# Spanungsversorgung.net
KiCad netlist of a schematic drawn in Altium Designer
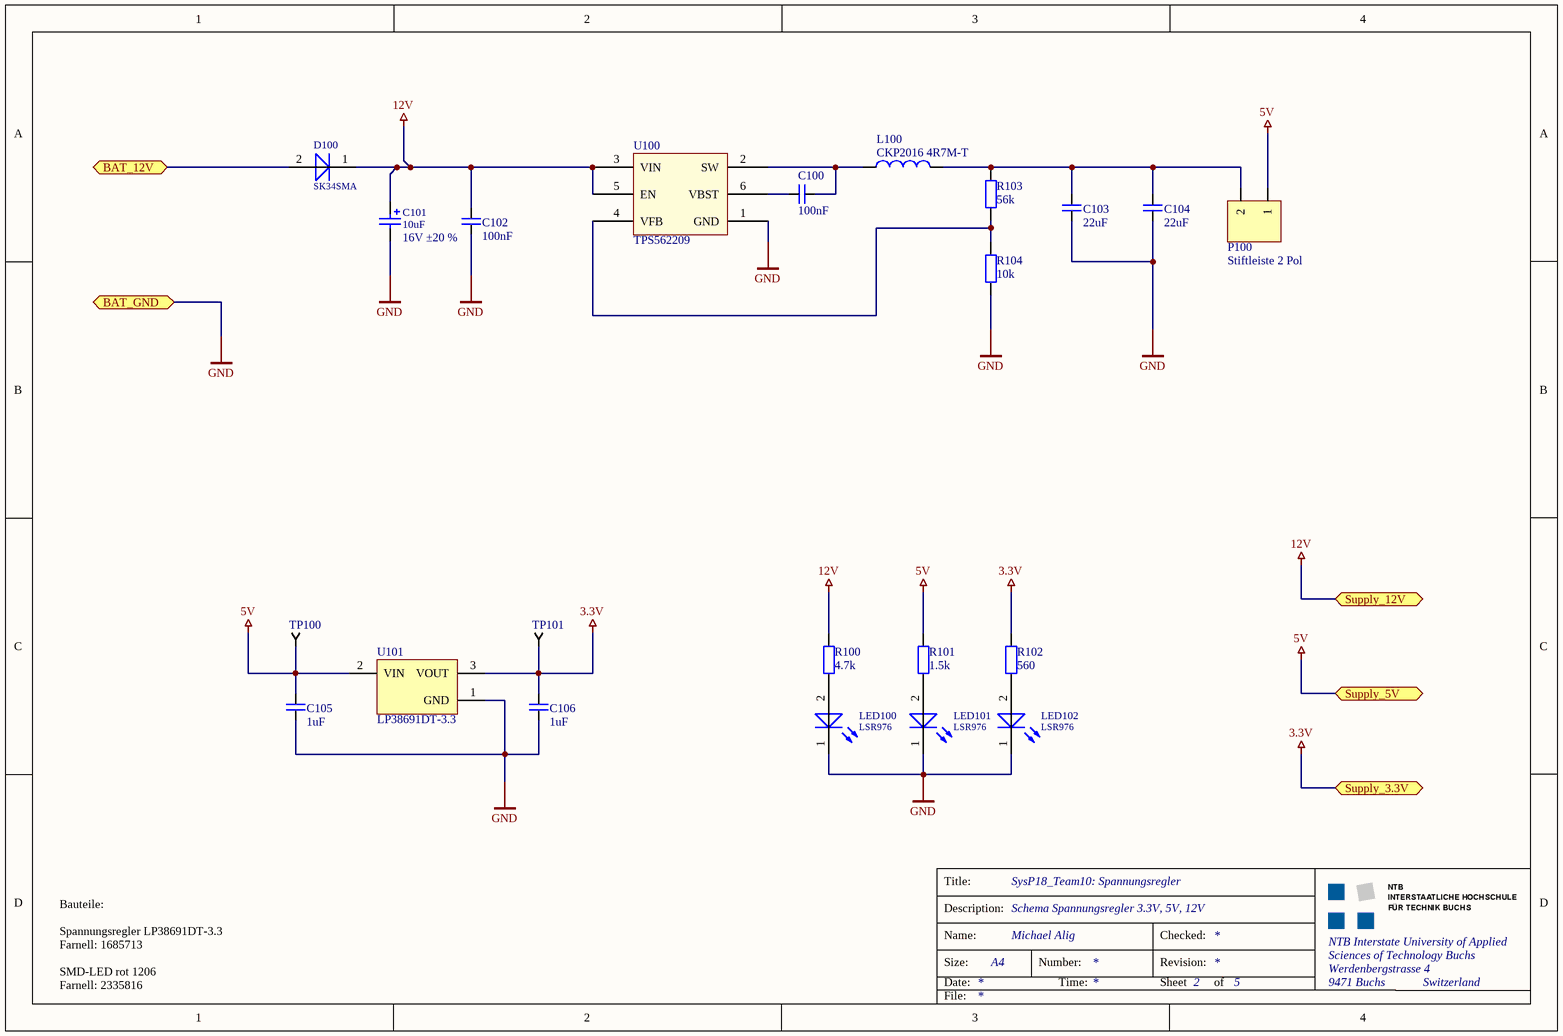
[diagram p0: Spanungsversorgung.SchDoc]

(export (version "E")
  (design (tool "Eeschema 10.0.6"))
  (components
    (comp (ref "C100")
      (value "100nF")
      (footprint "CAPC0805")
      (description "X7R MLCC 0805 (2012 Metric)")
      (fields (field (name "TOLERANCE") "10%"))
      (libsource (lib "Motorentreiber") (part "C Bipolar 0805"))
    )
    (comp (ref "C101")
      (value "10uF")
      (footprint "CDE_CAP AVE CODE D_H")
      (description "Aluminum Electrolytic Capacitors for Filtering and Bypass, 47uF, 16V")
      (fields
        (field (name "MANUFACTURER") "Cornell Dubilier")
        (field (name "VALUEADDON") "16V ±20 %")
        (field (name "Comment") "AVE476M16D16T-F")
        (field (name "PUBLISHER") "Stefan Ursella, M.Eng")
      )
      (libsource (lib "Motorentreiber") (part "CDE_AVE476M16D16T-F_AVE CODE D"))
    )
    (comp (ref "C102")
      (value "100nF")
      (footprint "CAPC0805")
      (description "X7R MLCC 0805 (2012 Metric)")
      (fields (field (name "TOLERANCE") "10%"))
      (libsource (lib "Motorentreiber") (part "C Bipolar 0805"))
    )
    (comp (ref "C103")
      (value "22uF")
      (footprint "CAPC1206")
      (description "X7R MLCC 1206 (3016 Metric)")
      (fields (field (name "TOLERANCE") "10%"))
      (libsource (lib "Motorentreiber") (part "C Bipolar 1206"))
    )
    (comp (ref "C104")
      (value "22uF")
      (footprint "CAPC1206")
      (description "X7R MLCC 1206 (3016 Metric)")
      (fields (field (name "TOLERANCE") "10%"))
      (libsource (lib "Motorentreiber") (part "C Bipolar 1206"))
    )
    (comp (ref "C105")
      (value "1uF")
      (footprint "CAPC0805")
      (description "X7R MLCC 0805 (2012 Metric)")
      (fields (field (name "TOLERANCE") "10%"))
      (libsource (lib "Motorentreiber") (part "C Bipolar 0805"))
    )
    (comp (ref "C106")
      (value "1uF")
      (footprint "CAPC0805")
      (description "X7R MLCC 0805 (2012 Metric)")
      (fields (field (name "TOLERANCE") "10%"))
      (libsource (lib "Motorentreiber") (part "C Bipolar 0805"))
    )
    (comp (ref "D100")
      (value "SK34SMA")
      (footprint "DIOTEC_DO-214AC_1K2A_2_H")
      (fields
        (field (name "MANUFACTURER") "Diotec Semiconductor")
        (field (name "PUBLISHER") "Stefan Ursella, M.Eng")
      )
      (libsource (lib "Motorentreiber") (part "DIOTEC_SK34SMA_DO-214AC"))
    )
    (comp (ref "L100")
      (value "CKP2016 4R7M-T")
      (footprint "IND0806")
      (description "MULTILAYER CHIP POWER INDUCTORS")
      (libsource (lib "Motorentreiber") (part "L"))
    )
    (comp (ref "LED100")
      (value "LSR976")
      (footprint "CAPC1206")
      (description "Hyper ChipLED, Red,")
      (fields (field (name "MANUFACTURER") "OSRAM") (field (name "PUBLISHER") "Stefan Ursella, M.Eng"))
      (libsource (lib "SysP2015") (part "OSR_LSR976_0805(1K2A)"))
    )
    (comp (ref "LED101")
      (value "LSR976")
      (footprint "CAPC1206")
      (description "Hyper ChipLED, Red,")
      (fields (field (name "MANUFACTURER") "OSRAM") (field (name "PUBLISHER") "Stefan Ursella, M.Eng"))
      (libsource (lib "SysP2015") (part "OSR_LSR976_0805(1K2A)"))
    )
    (comp (ref "LED102")
      (value "LSR976")
      (footprint "CAPC1206")
      (description "Hyper ChipLED, Red,")
      (fields (field (name "MANUFACTURER") "OSRAM") (field (name "PUBLISHER") "Stefan Ursella, M.Eng"))
      (libsource (lib "SysP2015") (part "OSR_LSR976_0805(1K2A)"))
    )
    (comp (ref "P100")
      (value "Stiftleiste 2 Pol")
      (footprint "2Pin Header 2.54mm")
      (libsource (lib "altium-import") (part "root_3_2 Pin Connector_"))
    )
    (comp (ref "R100")
      (value "4.7k")
      (footprint "GEN_R0805_H")
      (description "generic resistor")
      (fields
        (field (name "MANUFACTURER") "Tbd")
        (field (name "Comment") "Generic")
        (field (name "PUBLISHER") "Altium Limited")
      )
      (libsource (lib "Motorentreiber") (part "GEN_R_2"))
    )
    (comp (ref "R101")
      (value "1.5k")
      (footprint "GEN_R0805_H")
      (description "generic resistor")
      (fields
        (field (name "MANUFACTURER") "Tbd")
        (field (name "Comment") "Generic")
        (field (name "PUBLISHER") "Altium Limited")
      )
      (libsource (lib "Motorentreiber") (part "GEN_R_2"))
    )
    (comp (ref "R102")
      (value "560")
      (footprint "GEN_R0805_H")
      (description "generic resistor")
      (fields
        (field (name "MANUFACTURER") "Tbd")
        (field (name "Comment") "Generic")
        (field (name "PUBLISHER") "Altium Limited")
      )
      (libsource (lib "Motorentreiber") (part "GEN_R_2"))
    )
    (comp (ref "R103")
      (value "56k")
      (footprint "GEN_R0805_H")
      (description "generic resistor")
      (fields
        (field (name "MANUFACTURER") "Tbd")
        (field (name "Comment") "Generic")
        (field (name "PUBLISHER") "Altium Limited")
      )
      (libsource (lib "Motorentreiber") (part "GEN_R_2"))
    )
    (comp (ref "R104")
      (value "10k")
      (footprint "GEN_R0805_H")
      (description "generic resistor")
      (fields
        (field (name "MANUFACTURER") "Tbd")
        (field (name "Comment") "Generic")
        (field (name "PUBLISHER") "Altium Limited")
      )
      (libsource (lib "Motorentreiber") (part "GEN_R_2"))
    )
    (comp (ref "TP100")
      (value "Testpoint xSmall")
      (footprint "TP_SMD_xsmall")
      (libsource (lib "Motorentreiber") (part "Testpoint small"))
    )
    (comp (ref "TP101")
      (value "Testpoint xSmall")
      (footprint "TP_SMD_xsmall")
      (libsource (lib "Motorentreiber") (part "Testpoint small"))
    )
    (comp (ref "U100")
      (value "TPS562209")
      (footprint "SOT23-6")
      (description "3-A Synchronous Step-Down Voltage Regulator")
      (libsource (lib "Motorentreiber") (part "TPS562209"))
    )
    (comp (ref "U101")
      (value "LP38691DT-3.3")
      (footprint "TO-92-TO3")
      (description "Low Quiescent Current LDO, 3-Pin TO-92, Extended TemperatureBAG")
      (fields (field (name "PUBLISHER") "Altium Limited"))
      (libsource (lib "Microchip Power Mgt Line Regulator") (part "MCP1700-1202E/TO"))
    )
  )
  (nets
    (net (code "1") (name "/BAT_12V") (class "Default")
      (node (ref "D100") (pin "2") (pinfunction "A_2") (pintype "passive"))
    )
    (net (code "2") (name "3.3V") (class "Default")
      (node (ref "C106") (pin "1") (pinfunction "1_1") (pintype "passive"))
      (node (ref "R102") (pin "2") (pinfunction "2_2") (pintype "passive"))
      (node (ref "TP101") (pin "1") (pinfunction "0_1") (pintype "passive"))
      (node (ref "U101") (pin "3") (pinfunction "VOUT_3") (pintype "power_in"))
    )
    (net (code "3") (name "5V") (class "Default")
      (node (ref "C105") (pin "1") (pinfunction "1_1") (pintype "passive"))
      (node (ref "P100") (pin "1") (pinfunction "1_1") (pintype "passive"))
      (node (ref "R101") (pin "2") (pinfunction "2_2") (pintype "passive"))
      (node (ref "TP100") (pin "1") (pinfunction "0_1") (pintype "passive"))
      (node (ref "U101") (pin "2") (pinfunction "VIN_2") (pintype "power_in"))
    )
    (net (code "4") (name "12V") (class "Default")
      (node (ref "C101") (pin "1") (pinfunction "Pos_1") (pintype "passive"))
      (node (ref "C102") (pin "1") (pinfunction "1_1") (pintype "passive"))
      (node (ref "D100") (pin "1") (pinfunction "K_1") (pintype "passive"))
      (node (ref "R100") (pin "2") (pinfunction "2_2") (pintype "passive"))
      (node (ref "U100") (pin "3") (pinfunction "VIN_3") (pintype "passive"))
      (node (ref "U100") (pin "5") (pinfunction "EN_5") (pintype "passive"))
    )
    (net (code "5") (name "GND") (class "Default")
      (node (ref "C101") (pin "2") (pinfunction "Neg_2") (pintype "passive"))
      (node (ref "C102") (pin "2") (pinfunction "2_2") (pintype "passive"))
      (node (ref "C103") (pin "1") (pinfunction "1_1") (pintype "passive"))
      (node (ref "C104") (pin "2") (pinfunction "2_2") (pintype "passive"))
      (node (ref "C105") (pin "2") (pinfunction "2_2") (pintype "passive"))
      (node (ref "C106") (pin "2") (pinfunction "2_2") (pintype "passive"))
      (node (ref "LED100") (pin "1") (pinfunction "K_1") (pintype "passive"))
      (node (ref "LED101") (pin "1") (pinfunction "K_1") (pintype "passive"))
      (node (ref "LED102") (pin "1") (pinfunction "K_1") (pintype "passive"))
      (node (ref "R104") (pin "1") (pinfunction "1_1") (pintype "passive"))
      (node (ref "U100") (pin "1") (pinfunction "GND_1") (pintype "passive"))
      (node (ref "U101") (pin "1") (pinfunction "GND_1") (pintype "power_in"))
    )
    (net (code "6") (name "Net-(C103-Pad2)") (class "Default")
      (node (ref "C103") (pin "2") (pinfunction "2_2") (pintype "passive"))
      (node (ref "C104") (pin "1") (pinfunction "1_1") (pintype "passive"))
      (node (ref "L100") (pin "2") (pinfunction "2_2") (pintype "passive"))
      (node (ref "P100") (pin "2") (pinfunction "2_2") (pintype "passive"))
      (node (ref "R103") (pin "2") (pinfunction "2_2") (pintype "passive"))
    )
    (net (code "7") (name "Net-(LED100-A)") (class "Default")
      (node (ref "LED100") (pin "2") (pinfunction "A_2") (pintype "passive"))
      (node (ref "R100") (pin "1") (pinfunction "1_1") (pintype "passive"))
    )
    (net (code "8") (name "Net-(LED101-A)") (class "Default")
      (node (ref "LED101") (pin "2") (pinfunction "A_2") (pintype "passive"))
      (node (ref "R101") (pin "1") (pinfunction "1_1") (pintype "passive"))
    )
    (net (code "9") (name "Net-(LED102-A)") (class "Default")
      (node (ref "LED102") (pin "2") (pinfunction "A_2") (pintype "passive"))
      (node (ref "R102") (pin "1") (pinfunction "1_1") (pintype "passive"))
    )
    (net (code "10") (name "Net-(U100-SW)") (class "Default")
      (node (ref "C100") (pin "2") (pinfunction "2_2") (pintype "passive"))
      (node (ref "L100") (pin "1") (pinfunction "1_1") (pintype "passive"))
      (node (ref "U100") (pin "2") (pinfunction "SW_2") (pintype "passive"))
    )
    (net (code "11") (name "Net-(U100-VBST)") (class "Default")
      (node (ref "C100") (pin "1") (pinfunction "1_1") (pintype "passive"))
      (node (ref "U100") (pin "6") (pinfunction "VBST_6") (pintype "passive"))
    )
    (net (code "12") (name "Net-(U100-VFB)") (class "Default")
      (node (ref "R103") (pin "1") (pinfunction "1_1") (pintype "passive"))
      (node (ref "R104") (pin "2") (pinfunction "2_2") (pintype "passive"))
      (node (ref "U100") (pin "4") (pinfunction "VFB_4") (pintype "passive"))
    )
  )
)
